# CH32V002D4U6.net
KiCad netlist of a schematic drawn in Altium Designer
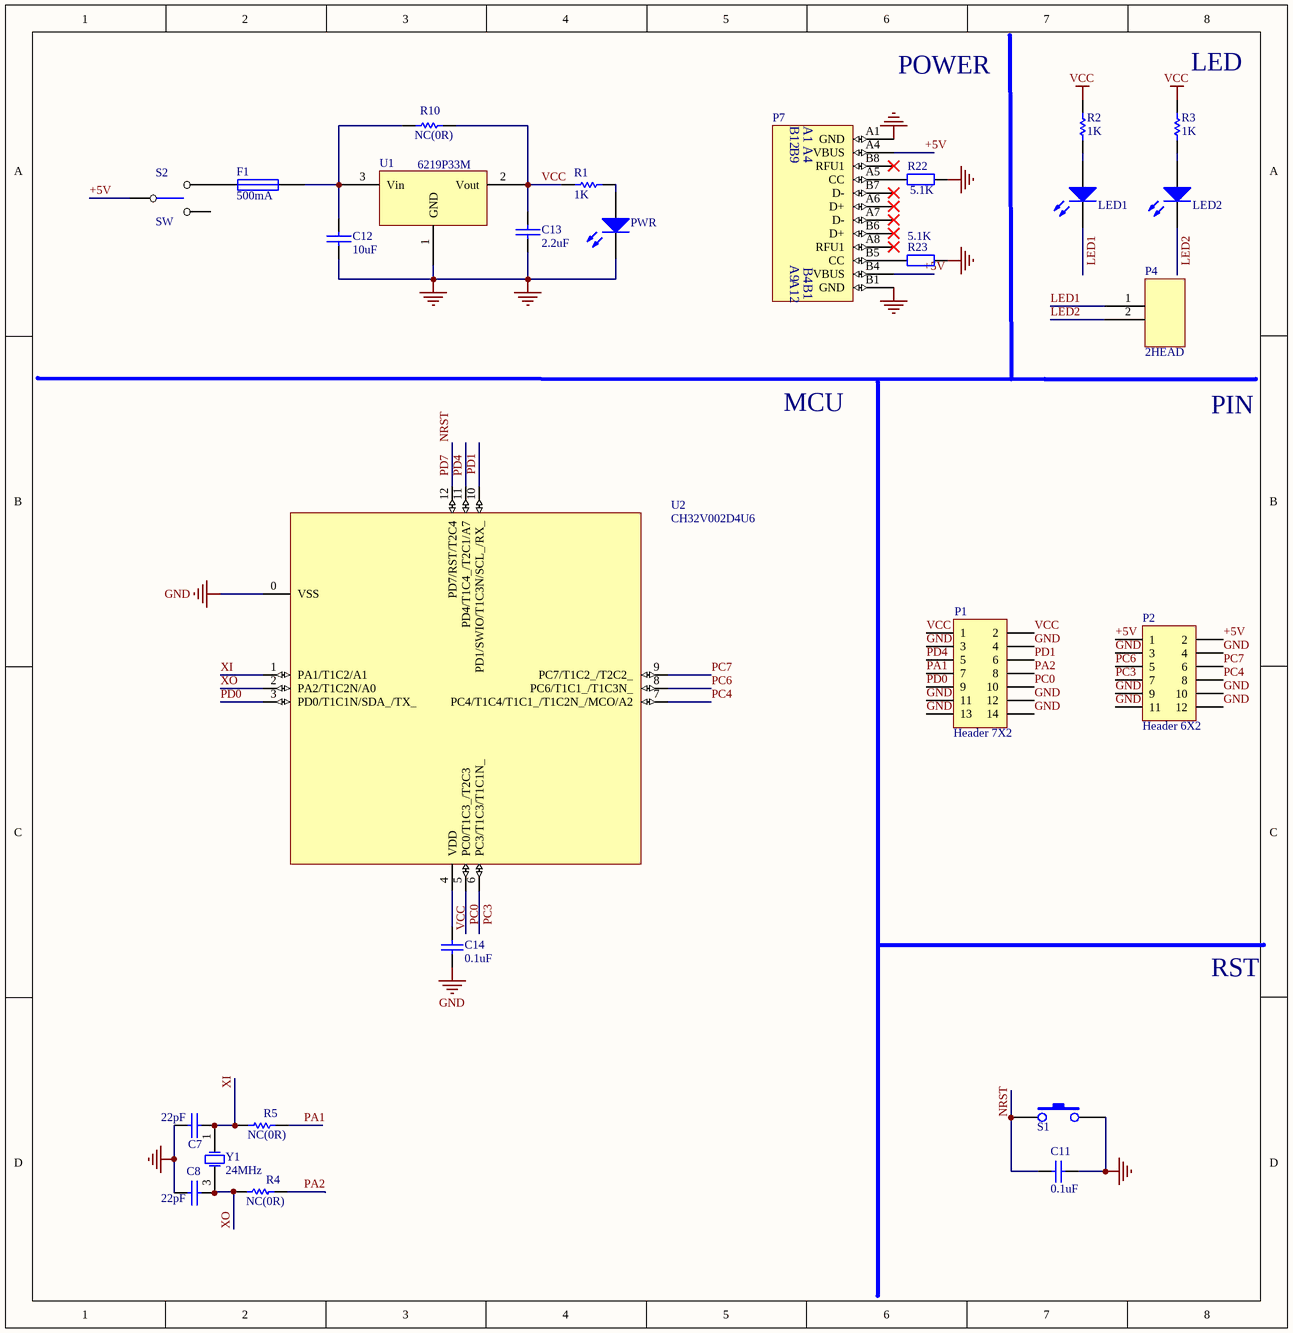
[diagram p0: CH32V002D4U6.SchDoc]

(export (version "E")
  (design (tool "Eeschema 10.0.6"))
  (components
    (comp (ref "C7")
      (value "22pF")
      (footprint "0402_C")
      (description "Capacitor")
      (libsource (lib "*") (part "CAP"))
    )
    (comp (ref "C8")
      (value "22pF")
      (footprint "0402_C")
      (description "Capacitor")
      (libsource (lib "*") (part "CAP"))
    )
    (comp (ref "C11")
      (value "0.1uF")
      (footprint "0402_C")
      (description "Capacitor")
      (fields (field (name "PUBLISHER") "Altium Limited"))
      (libsource (lib "*") (part "Cap"))
    )
    (comp (ref "C12")
      (value "10uF")
      (footprint "0603_C")
      (description "Capacitor")
      (libsource (lib "wch_sch_others") (part "CAP"))
    )
    (comp (ref "C13")
      (value "2.2uF")
      (footprint "0402_C")
      (description "Capacitor")
      (libsource (lib "wch_sch_others") (part "CAP"))
    )
    (comp (ref "C14")
      (value "0.1uF")
      (footprint "0603_C")
      (description "Capacitor")
      (fields (field (name "PUBLISHER") "Altium Limited"))
      (libsource (lib "*") (part "Cap"))
    )
    (comp (ref "F1")
      (value "500mA")
      (footprint "0603")
      (description "Fuse")
      (libsource (lib "*") (part "FUSE1"))
    )
    (comp (ref "LED1")
      (value "LED1   blue")
      (footprint "0603+")
      (description "Typical INFRARED GaAs LED")
      (fields (field (name "PUBLISHER") "Altium Limited"))
      (libsource (lib "*") (part "LED0"))
    )
    (comp (ref "LED2")
      (value "LED2  blue")
      (footprint "0603+")
      (description "Typical INFRARED GaAs LED")
      (fields (field (name "PUBLISHER") "Altium Limited"))
      (libsource (lib "*") (part "LED0"))
    )
    (comp (ref "P1")
      (value "Header 7X2")
      (footprint "HDR2X7")
      (description "Header, 7-Pin, Dual row")
      (fields (field (name "PUBLISHER") "Altium Limited"))
      (libsource (lib "Miscellaneous Connectors") (part "Header 7X2"))
    )
    (comp (ref "P2")
      (value "Header 6X2")
      (footprint "HDR2X6")
      (description "Header, 6-Pin, Dual row")
      (fields (field (name "PUBLISHER") "Altium Limited"))
      (libsource (lib "Miscellaneous Connectors") (part "Header 6X2"))
    )
    (comp (ref "P4") (value "2HEAD") (footprint "SIP2-2.54mm") (libsource (lib "*") (part "2HEAD")))
    (comp (ref "P7")
      (value "TYPE-C")
      (footprint "TYPE-C-Receptacle-2.0")
      (libsource (lib "*") (part "TYPE-C1"))
    )
    (comp (ref "PWR")
      (value "POWER  red")
      (footprint "0603+")
      (description "Typical INFRARED GaAs LED")
      (fields (field (name "PUBLISHER") "Altium Limited"))
      (libsource (lib "") (part "LED0_1"))
    )
    (comp (ref "R1")
      (value "1K")
      (footprint "0402")
      (description "Semiconductor Resistor")
      (fields (field (name "PUBLISHER") "Altium Limited"))
      (libsource (lib "*") (part "Res Semi"))
    )
    (comp (ref "R2")
      (value "1K")
      (footprint "0402")
      (description "Semiconductor Resistor")
      (fields (field (name "PUBLISHER") "Altium Limited"))
      (libsource (lib "*") (part "Res Semi"))
    )
    (comp (ref "R3")
      (value "1K")
      (footprint "0402")
      (description "Semiconductor Resistor")
      (fields (field (name "PUBLISHER") "Altium Limited"))
      (libsource (lib "*") (part "Res Semi"))
    )
    (comp (ref "R4")
      (value "NC(0R)")
      (footprint "0402")
      (description "Semiconductor Resistor")
      (fields (field (name "Comment") "0R") (field (name "PUBLISHER") "Altium Limited"))
      (libsource (lib "*") (part "Res Semi"))
    )
    (comp (ref "R5")
      (value "NC(0R)")
      (footprint "0402")
      (description "Semiconductor Resistor")
      (fields (field (name "Comment") "0R") (field (name "PUBLISHER") "Altium Limited"))
      (libsource (lib "*") (part "Res Semi"))
    )
    (comp (ref "R10")
      (value "NC(0R)")
      (footprint "0402")
      (description "Semiconductor Resistor")
      (fields (field (name "Comment") "0R") (field (name "PUBLISHER") "Altium Limited"))
      (libsource (lib "*") (part "Res Semi"))
    )
    (comp (ref "R22")
      (value "5.1K")
      (footprint "0402")
      (description "Resistor")
      (libsource (lib "Miscellaneous Devices") (part "Res2"))
    )
    (comp (ref "R23")
      (value "5.1K")
      (footprint "0402")
      (description "Resistor")
      (libsource (lib "Miscellaneous Devices") (part "Res2"))
    )
    (comp (ref "S1") (value "NRST") (footprint "SMD_6.1x3.65x2.5mm-KEY") (libsource (lib "*") (part "KEY")))
    (comp (ref "S2") (value "SW") (footprint "SW1") (libsource (lib "*") (part "SW")))
    (comp (ref "U1")
      (value "6219P33M")
      (footprint "SOT-23")
      (libsource (lib "wch_sch_others") (part "6219P33M"))
    )
    (comp (ref "U2")
      (value "CH32V002D4U6")
      (footprint "QFN12_2X2")
      (description "RISC-V MCU, 48MHz, ADC/UART/I2C")
      (libsource (lib "DHXXXSCH") (part "CH32V002D4U6"))
    )
    (comp (ref "Y1")
      (value "24MHz")
      (footprint "XT3225")
      (description "Crystal Oscillator")
      (fields (field (name "PUBLISHER") "Altium Limited"))
      (libsource (lib "*") (part "XTAL"))
    )
  )
  (nets
    (net (code "1") (name "/+5V") (class "Default")
      (node (ref "P2") (pin "1") (pinfunction "1_1") (pintype "passive"))
      (node (ref "P2") (pin "2") (pinfunction "2_2") (pintype "passive"))
      (node (ref "P7") (pin "A4") (pinfunction "VBUS_A4") (pintype "bidirectional"))
      (node (ref "P7") (pin "B4") (pinfunction "VBUS_B4") (pintype "bidirectional"))
      (node (ref "S2") (pin "1") (pinfunction "1_1") (pintype "passive"))
    )
    (net (code "2") (name "/LED1") (class "Default")
      (node (ref "LED1") (pin "2") (pinfunction "K_2") (pintype "passive"))
      (node (ref "P4") (pin "1") (pintype "passive"))
    )
    (net (code "3") (name "/LED2") (class "Default")
      (node (ref "LED2") (pin "2") (pinfunction "K_2") (pintype "passive"))
      (node (ref "P4") (pin "2") (pintype "passive"))
    )
    (net (code "4") (name "/NRST") (class "Default")
      (node (ref "C11") (pin "2") (pinfunction "2_2") (pintype "passive"))
      (node (ref "S1") (pin "1") (pinfunction "1_1") (pintype "passive"))
      (node (ref "U2") (pin "12") (pinfunction "PD7/RST/T2C4_12") (pintype "bidirectional"))
    )
    (net (code "5") (name "/PA1") (class "Default")
      (node (ref "P1") (pin "7") (pinfunction "7_7") (pintype "passive"))
      (node (ref "R5") (pin "2") (pinfunction "2_2") (pintype "passive"))
    )
    (net (code "6") (name "/PA2") (class "Default")
      (node (ref "P1") (pin "8") (pinfunction "8_8") (pintype "passive"))
      (node (ref "R4") (pin "2") (pinfunction "2_2") (pintype "passive"))
    )
    (net (code "7") (name "/PC0") (class "Default")
      (node (ref "P1") (pin "10") (pinfunction "10_10") (pintype "passive"))
      (node (ref "U2") (pin "5") (pinfunction "PC0/T1C3_/T2C3_5") (pintype "bidirectional"))
    )
    (net (code "8") (name "/PC3") (class "Default")
      (node (ref "P2") (pin "7") (pinfunction "7_7") (pintype "passive"))
      (node (ref "U2") (pin "6") (pinfunction "PC3/T1C3/T1C1N__6") (pintype "bidirectional"))
    )
    (net (code "9") (name "/PC4") (class "Default")
      (node (ref "P2") (pin "8") (pinfunction "8_8") (pintype "passive"))
      (node (ref "U2") (pin "7") (pinfunction "PC4/T1C4/T1C1_/T1C2N_/MCO/A2_7") (pintype "bidirectional"))
    )
    (net (code "10") (name "/PC6") (class "Default")
      (node (ref "P2") (pin "5") (pinfunction "5_5") (pintype "passive"))
      (node (ref "U2") (pin "8") (pinfunction "PC6/T1C1_/T1C3N__8") (pintype "bidirectional"))
    )
    (net (code "11") (name "/PC7") (class "Default")
      (node (ref "P2") (pin "6") (pinfunction "6_6") (pintype "passive"))
      (node (ref "U2") (pin "9") (pinfunction "PC7/T1C2_/T2C2__9") (pintype "bidirectional"))
    )
    (net (code "12") (name "/PD0") (class "Default")
      (node (ref "P1") (pin "9") (pinfunction "9_9") (pintype "passive"))
      (node (ref "U2") (pin "3") (pinfunction "PD0/T1C1N/SDA_/TX__3") (pintype "bidirectional"))
    )
    (net (code "13") (name "/PD1") (class "Default")
      (node (ref "P1") (pin "6") (pinfunction "6_6") (pintype "passive"))
      (node (ref "U2") (pin "10") (pinfunction "PD1/SWIO/T1C3N/SCL_/RX__10") (pintype "bidirectional"))
    )
    (net (code "14") (name "/PD4") (class "Default")
      (node (ref "P1") (pin "5") (pinfunction "5_5") (pintype "passive"))
      (node (ref "U2") (pin "11") (pinfunction "PD4/T1C4_/T2C1/A7_11") (pintype "bidirectional"))
    )
    (net (code "15") (name "/XI") (class "Default")
      (node (ref "C7") (pin "2") (pinfunction "2_2") (pintype "passive"))
      (node (ref "R5") (pin "1") (pinfunction "1_1") (pintype "passive"))
      (node (ref "U2") (pin "1") (pinfunction "PA1/T1C2/A1_1") (pintype "bidirectional"))
      (node (ref "Y1") (pin "1") (pinfunction "OSC1_1") (pintype "passive"))
    )
    (net (code "16") (name "/XO") (class "Default")
      (node (ref "C8") (pin "2") (pinfunction "2_2") (pintype "passive"))
      (node (ref "R4") (pin "1") (pinfunction "1_1") (pintype "passive"))
      (node (ref "U2") (pin "2") (pinfunction "PA2/T1C2N/A0_2") (pintype "bidirectional"))
      (node (ref "Y1") (pin "3") (pinfunction "OSC2_3") (pintype "passive"))
    )
    (net (code "17") (name "GND") (class "Default")
      (node (ref "C11") (pin "1") (pinfunction "1_1") (pintype "passive"))
      (node (ref "C12") (pin "2") (pinfunction "2_2") (pintype "passive"))
      (node (ref "C13") (pin "1") (pinfunction "1_1") (pintype "passive"))
      (node (ref "C14") (pin "2") (pinfunction "2_2") (pintype "passive"))
      (node (ref "C7") (pin "1") (pinfunction "1_1") (pintype "passive"))
      (node (ref "C8") (pin "1") (pinfunction "1_1") (pintype "passive"))
      (node (ref "P1") (pin "11") (pinfunction "11_11") (pintype "passive"))
      (node (ref "P1") (pin "12") (pinfunction "12_12") (pintype "passive"))
      (node (ref "P1") (pin "13") (pinfunction "13_13") (pintype "passive"))
      (node (ref "P1") (pin "14") (pinfunction "14_14") (pintype "passive"))
      (node (ref "P1") (pin "3") (pinfunction "3_3") (pintype "passive"))
      (node (ref "P1") (pin "4") (pinfunction "4_4") (pintype "passive"))
      (node (ref "P2") (pin "10") (pinfunction "10_10") (pintype "passive"))
      (node (ref "P2") (pin "11") (pinfunction "11_11") (pintype "passive"))
      (node (ref "P2") (pin "12") (pinfunction "12_12") (pintype "passive"))
      (node (ref "P2") (pin "3") (pinfunction "3_3") (pintype "passive"))
      (node (ref "P2") (pin "4") (pinfunction "4_4") (pintype "passive"))
      (node (ref "P2") (pin "9") (pinfunction "9_9") (pintype "passive"))
      (node (ref "P7") (pin "A1") (pinfunction "GND_A1") (pintype "bidirectional"))
      (node (ref "P7") (pin "B1") (pinfunction "GND_B1") (pintype "bidirectional"))
      (node (ref "PWR") (pin "2") (pinfunction "K_2") (pintype "passive"))
      (node (ref "R22") (pin "2") (pinfunction "2_2") (pintype "passive"))
      (node (ref "R23") (pin "2") (pinfunction "2_2") (pintype "passive"))
      (node (ref "S1") (pin "2") (pinfunction "2_2") (pintype "passive"))
      (node (ref "U1") (pin "1") (pinfunction "GND_1") (pintype "passive"))
      (node (ref "U2") (pin "0") (pinfunction "VSS_0") (pintype "power_in"))
    )
    (net (code "18") (name "Net-(F1-Pad1)") (class "Default")
      (node (ref "F1") (pin "1") (pinfunction "1_1") (pintype "passive"))
      (node (ref "S2") (pin "3") (pinfunction "3_3") (pintype "passive"))
    )
    (net (code "19") (name "Net-(LED1-A)") (class "Default")
      (node (ref "LED1") (pin "1") (pinfunction "A_1") (pintype "passive"))
      (node (ref "R2") (pin "2") (pinfunction "2_2") (pintype "passive"))
    )
    (net (code "20") (name "Net-(LED2-A)") (class "Default")
      (node (ref "LED2") (pin "1") (pinfunction "A_1") (pintype "passive"))
      (node (ref "R3") (pin "2") (pinfunction "2_2") (pintype "passive"))
    )
    (net (code "21") (name "Net-(P7-CC-PadA5)") (class "Default")
      (node (ref "P7") (pin "A5") (pinfunction "CC_A5") (pintype "bidirectional"))
      (node (ref "R22") (pin "1") (pinfunction "1_1") (pintype "passive"))
    )
    (net (code "22") (name "Net-(P7-CC-PadB5)") (class "Default")
      (node (ref "P7") (pin "B5") (pinfunction "CC_B5") (pintype "bidirectional"))
      (node (ref "R23") (pin "1") (pinfunction "1_1") (pintype "passive"))
    )
    (net (code "23") (name "Net-(PWR-A)") (class "Default")
      (node (ref "PWR") (pin "1") (pinfunction "A_1") (pintype "passive"))
      (node (ref "R1") (pin "1") (pinfunction "1_1") (pintype "passive"))
    )
    (net (code "24") (name "Net-(U1-Vin)") (class "Default")
      (node (ref "C12") (pin "1") (pinfunction "1_1") (pintype "passive"))
      (node (ref "F1") (pin "2") (pinfunction "2_2") (pintype "passive"))
      (node (ref "R10") (pin "1") (pinfunction "1_1") (pintype "passive"))
      (node (ref "U1") (pin "3") (pinfunction "Vin_3") (pintype "passive"))
    )
    (net (code "25") (name "VCC") (class "Default")
      (node (ref "C13") (pin "2") (pinfunction "2_2") (pintype "passive"))
      (node (ref "C14") (pin "1") (pinfunction "1_1") (pintype "passive"))
      (node (ref "P1") (pin "1") (pinfunction "1_1") (pintype "passive"))
      (node (ref "P1") (pin "2") (pinfunction "2_2") (pintype "passive"))
      (node (ref "R1") (pin "2") (pinfunction "2_2") (pintype "passive"))
      (node (ref "R10") (pin "2") (pinfunction "2_2") (pintype "passive"))
      (node (ref "R2") (pin "1") (pinfunction "1_1") (pintype "passive"))
      (node (ref "R3") (pin "1") (pinfunction "1_1") (pintype "passive"))
      (node (ref "U1") (pin "2") (pinfunction "Vout_2") (pintype "passive"))
      (node (ref "U2") (pin "4") (pinfunction "VDD_4") (pintype "power_in"))
    )
    (net (code "26") (name "unconnected-(P7-D+-PadA6)") (class "Default")
      (node (ref "P7") (pin "A6") (pinfunction "D+_A6") (pintype "bidirectional+no_connect"))
    )
    (net (code "27") (name "unconnected-(P7-D+-PadB6)") (class "Default")
      (node (ref "P7") (pin "B6") (pinfunction "D+_B6") (pintype "bidirectional+no_connect"))
    )
    (net (code "28") (name "unconnected-(P7-D--PadA7)") (class "Default")
      (node (ref "P7") (pin "A7") (pinfunction "D-_A7") (pintype "bidirectional+no_connect"))
    )
    (net (code "29") (name "unconnected-(P7-D--PadB7)") (class "Default")
      (node (ref "P7") (pin "B7") (pinfunction "D-_B7") (pintype "bidirectional+no_connect"))
    )
    (net (code "30") (name "unconnected-(P7-RFU1-PadA8)") (class "Default")
      (node (ref "P7") (pin "A8") (pinfunction "RFU1_A8") (pintype "bidirectional+no_connect"))
    )
    (net (code "31") (name "unconnected-(P7-RFU1-PadB8)") (class "Default")
      (node (ref "P7") (pin "B8") (pinfunction "RFU1_B8") (pintype "bidirectional+no_connect"))
    )
    (net (code "32") (name "unconnected-(S2-Pad2)") (class "Default")
      (node (ref "S2") (pin "2") (pinfunction "2_2") (pintype "passive"))
    )
  )
)
